# pico32_remote_v1_1.net
KiCad netlist of a schematic drawn in EAGLE
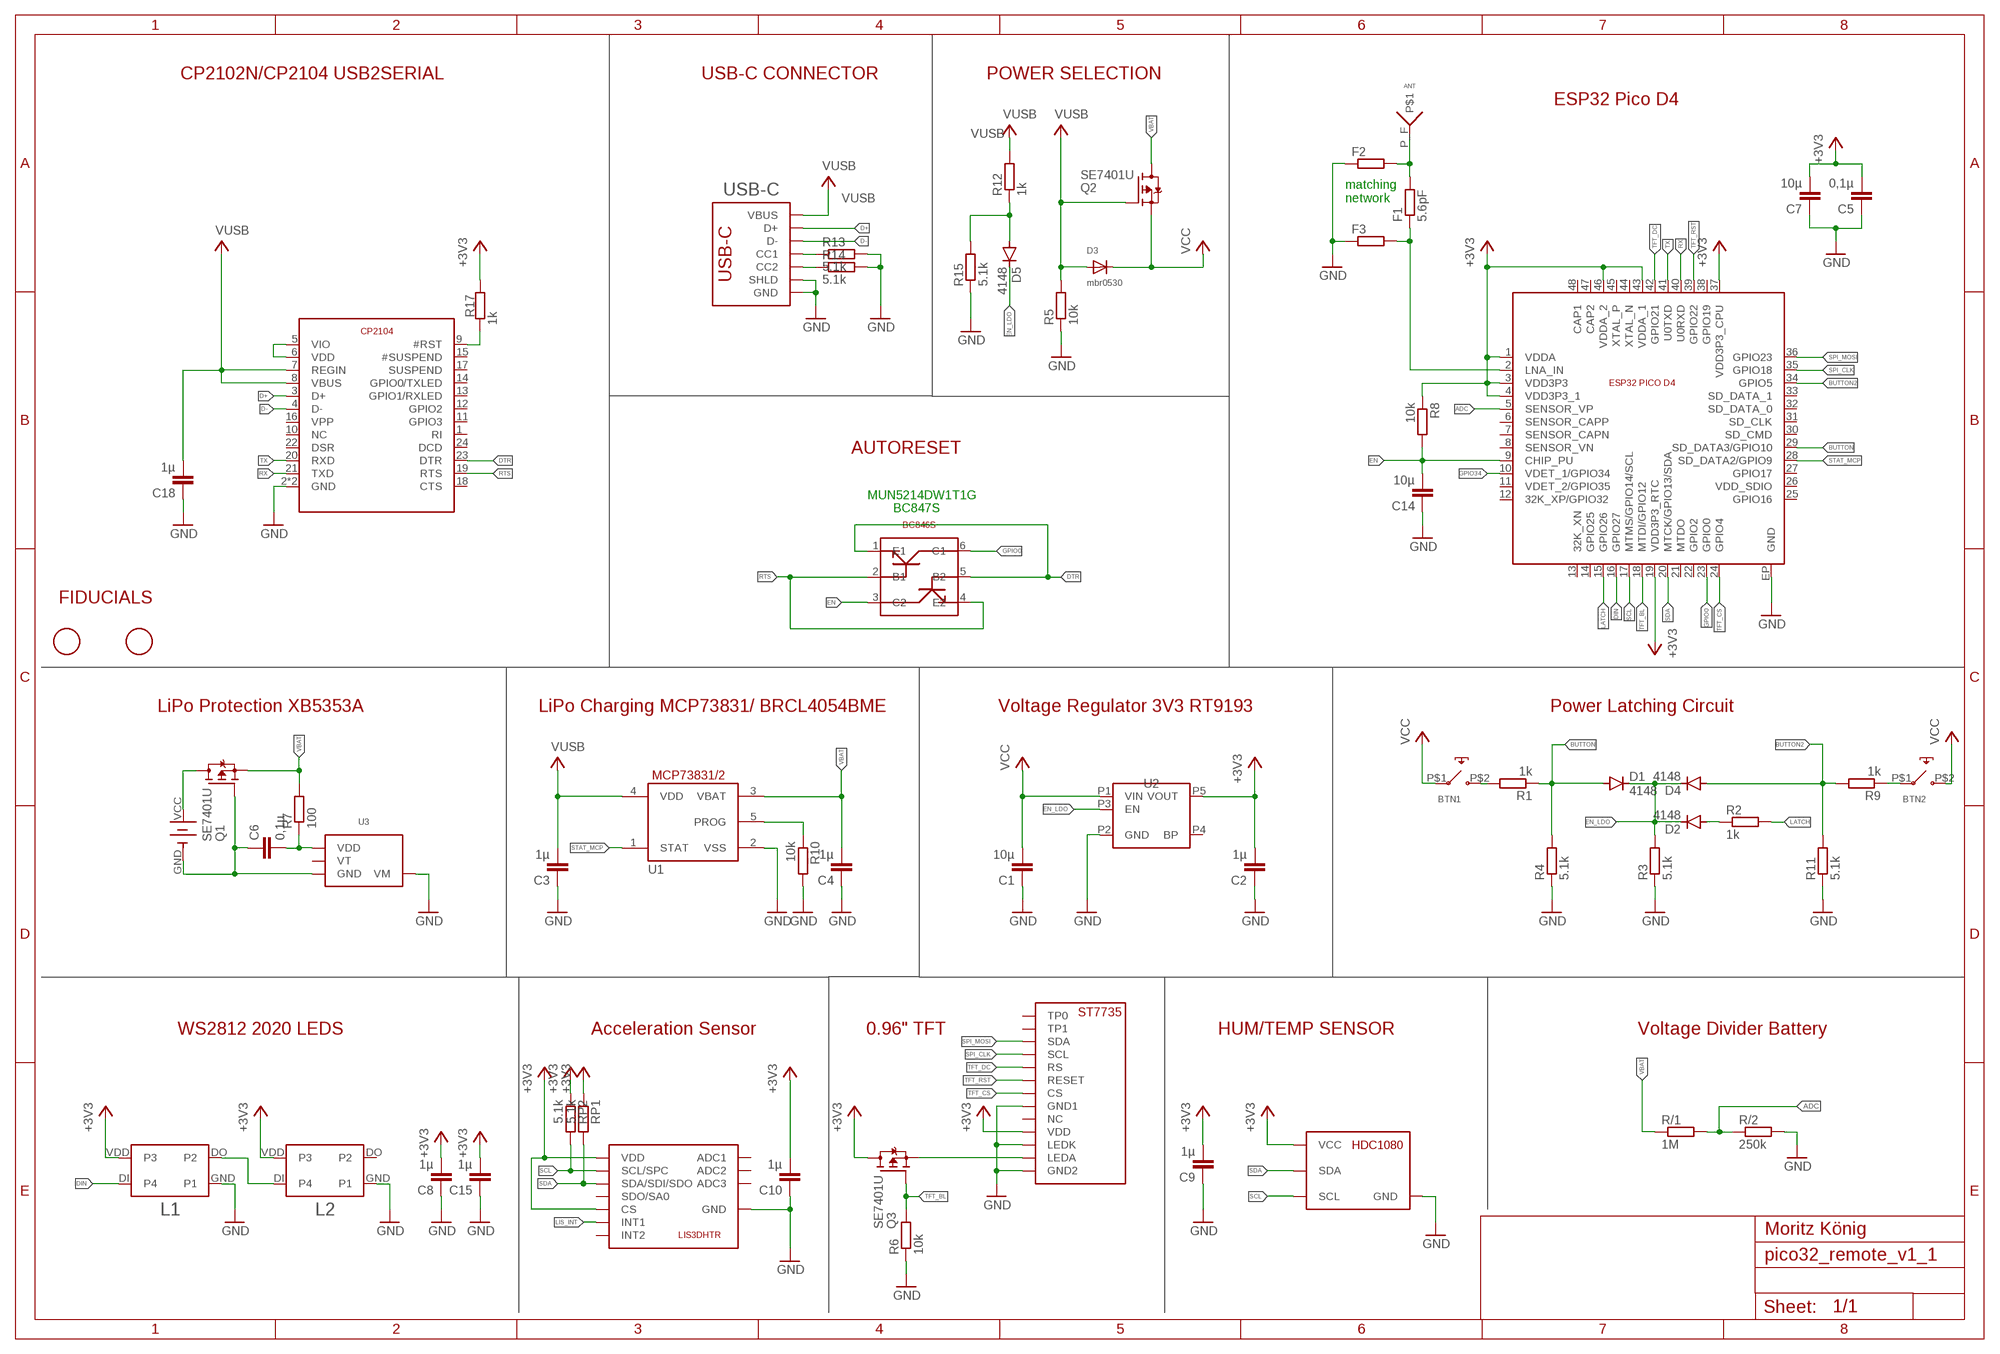
[diagram p0: schematic, sheet 1]

(export (version "E")
  (design (tool "Eeschema 10.0.6"))
  (components
    (comp (ref "ANT")
      (value "MOLEX_ANT_3D")
      (footprint "eagle-import:MOLEX_ANT_3D")
      (libsource (lib "eagle-import") (part "MOLEX_ANT_3D"))
    )
    (comp (ref "BTN1")
      (value "BUTTON_6X6_SILICON")
      (footprint "eagle-import:BUTTON_SILICON")
      (libsource (lib "eagle-import") (part "BUTTON_6X6_SILICON"))
    )
    (comp (ref "BTN2")
      (value "BUTTON_6X6_SILICON")
      (footprint "eagle-import:BUTTON_SILICON")
      (libsource (lib "eagle-import") (part "BUTTON_6X6_SILICON"))
    )
    (comp (ref "C1")
      (value "10µ")
      (footprint "eagle-import:C0603")
      (libsource (lib "eagle-import") (part "C-EU_WO_KEEPOUT"))
    )
    (comp (ref "C2")
      (value "1µ")
      (footprint "eagle-import:C0603")
      (libsource (lib "eagle-import") (part "C-EU_WO_KEEPOUT"))
    )
    (comp (ref "C3")
      (value "1µ")
      (footprint "eagle-import:R0402")
      (libsource (lib "eagle-import") (part "C-EU-0402-WOKEEPOUT_R"))
    )
    (comp (ref "C4")
      (value "1µ")
      (footprint "eagle-import:R0402")
      (libsource (lib "eagle-import") (part "C-EU-0402-WOKEEPOUT_R"))
    )
    (comp (ref "C5")
      (value "0,1µ")
      (footprint "eagle-import:C0603")
      (libsource (lib "eagle-import") (part "C-EU_WO_KEEPOUT"))
    )
    (comp (ref "C6")
      (value "0,1µ")
      (footprint "eagle-import:R0402")
      (libsource (lib "eagle-import") (part "C-EU-0402-WOKEEPOUT_R"))
    )
    (comp (ref "C7")
      (value "10µ")
      (footprint "eagle-import:C0603")
      (libsource (lib "eagle-import") (part "C-EU_WO_KEEPOUT"))
    )
    (comp (ref "C8")
      (value "1µ")
      (footprint "eagle-import:R0402")
      (libsource (lib "eagle-import") (part "C-EU-0402-WOKEEPOUT_R"))
    )
    (comp (ref "C9")
      (value "1µ")
      (footprint "eagle-import:R0402")
      (libsource (lib "eagle-import") (part "C-EU-0402-WOKEEPOUT_R"))
    )
    (comp (ref "C10")
      (value "1µ")
      (footprint "eagle-import:R0402")
      (libsource (lib "eagle-import") (part "C-EU-0402-WOKEEPOUT_R"))
    )
    (comp (ref "C14")
      (value "10µ")
      (footprint "eagle-import:C0402K")
      (libsource (lib "eagle-import") (part "C-EUC0402K"))
    )
    (comp (ref "C15")
      (value "1µ")
      (footprint "eagle-import:R0402")
      (libsource (lib "eagle-import") (part "C-EU-0402-WOKEEPOUT_R"))
    )
    (comp (ref "C18")
      (value "1µ")
      (footprint "eagle-import:R0402")
      (libsource (lib "eagle-import") (part "C-EU-0402-WOKEEPOUT_R"))
    )
    (comp (ref "D1")
      (value "4148")
      (footprint "eagle-import:SOD523")
      (libsource (lib "eagle-import") (part "DIODE-SOD523"))
    )
    (comp (ref "D2")
      (value "4148")
      (footprint "eagle-import:SOD523")
      (libsource (lib "eagle-import") (part "DIODE-SOD523"))
    )
    (comp (ref "D3")
      (value "mbr0530")
      (footprint "eagle-import:SOD-123FL")
      (libsource (lib "eagle-import") (part "DIODE_SOD-123FL"))
    )
    (comp (ref "D4")
      (value "4148")
      (footprint "eagle-import:SOD523")
      (libsource (lib "eagle-import") (part "DIODE-SOD523"))
    )
    (comp (ref "D5")
      (value "4148")
      (footprint "eagle-import:SOD523")
      (libsource (lib "eagle-import") (part "DIODE-SOD523"))
    )
    (comp (ref "ESP32")
      (value "ESP32_PICO_D4_LP")
      (footprint "eagle-import:QFN-48_LONG")
      (libsource (lib "eagle-import") (part "ESP32_PICO_D4_LP"))
    )
    (comp (ref "F1")
      (value "5.6pF")
      (footprint "eagle-import:R0402")
      (libsource (lib "eagle-import") (part "R-EU-0402-WOKEEPOUT"))
    )
    (comp (ref "F2")
      (value "R-EU-0402-WOKEEPOUT")
      (footprint "eagle-import:R0402")
      (libsource (lib "eagle-import") (part "R-EU-0402-WOKEEPOUT"))
    )
    (comp (ref "F3")
      (value "R-EU-0402-WOKEEPOUT")
      (footprint "eagle-import:R0402")
      (libsource (lib "eagle-import") (part "R-EU-0402-WOKEEPOUT"))
    )
    (comp (ref "L1")
      (value "WS2812_2020")
      (footprint "eagle-import:WS2812_2020")
      (libsource (lib "eagle-import") (part "WS2812_2020"))
    )
    (comp (ref "L2")
      (value "WS2812_2020")
      (footprint "eagle-import:WS2812_2020")
      (libsource (lib "eagle-import") (part "WS2812_2020"))
    )
    (comp (ref "Q1")
      (value "SE7401U")
      (footprint "eagle-import:SOT323")
      (libsource (lib "eagle-import") (part "SE7401U"))
    )
    (comp (ref "Q2")
      (value "SE7401U")
      (footprint "eagle-import:SOT323")
      (libsource (lib "eagle-import") (part "SE7401U"))
    )
    (comp (ref "Q3")
      (value "SE7401U")
      (footprint "eagle-import:SOT323")
      (libsource (lib "eagle-import") (part "SE7401U"))
    )
    (comp (ref "R/1")
      (value "1M")
      (footprint "eagle-import:R0402")
      (libsource (lib "eagle-import") (part "R-EU-0402-WOKEEPOUT"))
    )
    (comp (ref "R/2")
      (value "250k")
      (footprint "eagle-import:R0402")
      (libsource (lib "eagle-import") (part "R-EU-0402-WOKEEPOUT"))
    )
    (comp (ref "R1")
      (value "1k")
      (footprint "eagle-import:R0402")
      (libsource (lib "eagle-import") (part "R-EU-0402-WOKEEPOUT"))
    )
    (comp (ref "R2")
      (value "1k")
      (footprint "eagle-import:R0402")
      (libsource (lib "eagle-import") (part "R-EU-0402-WOKEEPOUT"))
    )
    (comp (ref "R3")
      (value "5.1k")
      (footprint "eagle-import:R0402")
      (libsource (lib "eagle-import") (part "R-EU-0402-WOKEEPOUT"))
    )
    (comp (ref "R4")
      (value "5.1k")
      (footprint "eagle-import:R0402")
      (libsource (lib "eagle-import") (part "R-EU-0402-WOKEEPOUT"))
    )
    (comp (ref "R5")
      (value "10k")
      (footprint "eagle-import:R0402")
      (libsource (lib "eagle-import") (part "R-EU-0402-WOKEEPOUT"))
    )
    (comp (ref "R6")
      (value "10k")
      (footprint "eagle-import:R0402")
      (libsource (lib "eagle-import") (part "R-EU-0402-WOKEEPOUT"))
    )
    (comp (ref "R7")
      (value "100")
      (footprint "eagle-import:R0402")
      (libsource (lib "eagle-import") (part "R-EU-0402-WOKEEPOUT"))
    )
    (comp (ref "R8")
      (value "10k")
      (footprint "eagle-import:R0402")
      (libsource (lib "eagle-import") (part "R-EU-0402-WOKEEPOUT"))
    )
    (comp (ref "R9")
      (value "1k")
      (footprint "eagle-import:R0402")
      (libsource (lib "eagle-import") (part "R-EU-0402-WOKEEPOUT"))
    )
    (comp (ref "R10")
      (value "10k")
      (footprint "eagle-import:R0402")
      (libsource (lib "eagle-import") (part "R-EU-0402-WOKEEPOUT"))
    )
    (comp (ref "R11")
      (value "5.1k")
      (footprint "eagle-import:R0402")
      (libsource (lib "eagle-import") (part "R-EU-0402-WOKEEPOUT"))
    )
    (comp (ref "R12")
      (value "1k")
      (footprint "eagle-import:R0402")
      (libsource (lib "eagle-import") (part "R-EU-0402-WOKEEPOUT"))
    )
    (comp (ref "R13")
      (value "5.1k")
      (footprint "eagle-import:R0402")
      (libsource (lib "eagle-import") (part "R-EU-0402-WOKEEPOUT"))
    )
    (comp (ref "R14")
      (value "5.1k")
      (footprint "eagle-import:R0402")
      (libsource (lib "eagle-import") (part "R-EU-0402-WOKEEPOUT"))
    )
    (comp (ref "R15")
      (value "5.1k")
      (footprint "eagle-import:R0402")
      (libsource (lib "eagle-import") (part "R-EU-0402-WOKEEPOUT"))
    )
    (comp (ref "R17")
      (value "1k")
      (footprint "eagle-import:R0402")
      (libsource (lib "eagle-import") (part "R-EU-0402-WOKEEPOUT"))
    )
    (comp (ref "RP1")
      (value "5.1k")
      (footprint "eagle-import:R0402")
      (libsource (lib "eagle-import") (part "R-EU-0402-WOKEEPOUT"))
    )
    (comp (ref "RP2")
      (value "5.1k")
      (footprint "eagle-import:R0402")
      (libsource (lib "eagle-import") (part "R-EU-0402-WOKEEPOUT"))
    )
    (comp (ref "U$2")
      (value "2450_BATTERYHOLDER_SMD")
      (footprint "eagle-import:2450_BATTERYHOLDER_SMD")
      (libsource (lib "eagle-import") (part "2450_BATTERYHOLDER_SMD"))
    )
    (comp (ref "U$4")
      (value "ST7735_096TFT_TWISTED")
      (footprint "eagle-import:ST7735_096TFT_TWISTED")
      (libsource (lib "eagle-import") (part "ST7735_096TFT_TWISTED"))
    )
    (comp (ref "U$6")
      (value "FIDUCIAL")
      (footprint "eagle-import:FIDUCIAL_1MM")
      (libsource (lib "eagle-import") (part "FIDUCIAL"))
    )
    (comp (ref "U$7")
      (value "FIDUCIAL")
      (footprint "eagle-import:FIDUCIAL_1MM")
      (libsource (lib "eagle-import") (part "FIDUCIAL"))
    )
    (comp (ref "U1")
      (value "BRCL4054BME")
      (footprint "eagle-import:SOT23-5L")
      (libsource (lib "eagle-import") (part "MCP73831/OT"))
    )
    (comp (ref "U2")
      (value "RT9193_SC70-5")
      (footprint "eagle-import:SC-70-5")
      (libsource (lib "eagle-import") (part "RT9193_SC70-5"))
    )
    (comp (ref "U3")
      (value "XB5353A")
      (footprint "eagle-import:SOT23-5")
      (libsource (lib "eagle-import") (part "XB5353A"))
    )
    (comp (ref "U4")
      (value "LIS3DHTR")
      (footprint "eagle-import:LGA_16_LIS3DHTR")
      (libsource (lib "eagle-import") (part "LIS3DHTR"))
    )
    (comp (ref "U5")
      (value "CP2102N")
      (footprint "eagle-import:QFN24-4X4")
      (libsource (lib "eagle-import") (part "CP2104"))
    )
    (comp (ref "U6")
      (value "MUN5214DW1T1G")
      (footprint "eagle-import:SOT363")
      (libsource (lib "eagle-import") (part "BC846S"))
    )
    (comp (ref "U7")
      (value "HDC1080")
      (footprint "eagle-import:WSON08_HDC1080")
      (libsource (lib "eagle-import") (part "HDC1080"))
    )
    (comp (ref "USB-C")
      (value "USB_C_C393939")
      (footprint "eagle-import:USBC_C393939")
      (libsource (lib "eagle-import") (part "USB_C_C393939"))
    )
  )
  (nets
    (net (code "1") (name "+3V3") (class "Default")
      (node (ref "C10") (pin "2") (pinfunction "2_2") (pintype "passive"))
      (node (ref "C15") (pin "2") (pinfunction "2_2") (pintype "passive"))
      (node (ref "C2") (pin "2") (pinfunction "2_2") (pintype "passive"))
      (node (ref "C5") (pin "2") (pinfunction "2_2") (pintype "passive"))
      (node (ref "C7") (pin "2") (pinfunction "2_2") (pintype "passive"))
      (node (ref "C8") (pin "2") (pinfunction "2_2") (pintype "passive"))
      (node (ref "C9") (pin "2") (pinfunction "2_2") (pintype "passive"))
      (node (ref "ESP32") (pin "1") (pinfunction "VDDA_1") (pintype "bidirectional"))
      (node (ref "ESP32") (pin "19") (pinfunction "VDD3P3_RTC_19") (pintype "bidirectional"))
      (node (ref "ESP32") (pin "3") (pinfunction "VDD3P3_3") (pintype "bidirectional"))
      (node (ref "ESP32") (pin "37") (pinfunction "VDD3P3_CPU_37") (pintype "bidirectional"))
      (node (ref "ESP32") (pin "4") (pinfunction "VDD3P3_1_4") (pintype "bidirectional"))
      (node (ref "ESP32") (pin "43") (pinfunction "VDDA_1_43") (pintype "bidirectional"))
      (node (ref "ESP32") (pin "46") (pinfunction "VDDA_2_46") (pintype "bidirectional"))
      (node (ref "L1") (pin "VDD") (pinfunction "P3_VDD") (pintype "bidirectional"))
      (node (ref "L2") (pin "VDD") (pinfunction "P3_VDD") (pintype "bidirectional"))
      (node (ref "Q3") (pin "3") (pinfunction "D_3") (pintype "passive"))
      (node (ref "R17") (pin "2") (pinfunction "2_2") (pintype "passive"))
      (node (ref "R8") (pin "1") (pinfunction "1_1") (pintype "passive"))
      (node (ref "RP1") (pin "1") (pinfunction "1_1") (pintype "passive"))
      (node (ref "RP2") (pin "1") (pinfunction "1_1") (pintype "passive"))
      (node (ref "U$4") (pin "P10") (pinfunction "VDD_P10") (pintype "bidirectional"))
      (node (ref "U2") (pin "P5") (pinfunction "VOUT_P5") (pintype "bidirectional"))
      (node (ref "U4") (pin "P$1") (pinfunction "VDD_P$1") (pintype "bidirectional"))
      (node (ref "U4") (pin "P$14") (pinfunction "VDD_P$14") (pintype "bidirectional"))
      (node (ref "U4") (pin "P$8") (pinfunction "CS_P$8") (pintype "bidirectional"))
      (node (ref "U7") (pin "P5") (pinfunction "VCC_P5") (pintype "bidirectional"))
    )
    (net (code "2") (name "ADC") (class "Default")
      (node (ref "ESP32") (pin "5") (pinfunction "SENSOR_VP_5") (pintype "bidirectional"))
      (node (ref "R/1") (pin "2") (pinfunction "2_2") (pintype "passive"))
      (node (ref "R/2") (pin "1") (pinfunction "1_1") (pintype "passive"))
    )
    (net (code "3") (name "BUTTON") (class "Default")
      (node (ref "D1") (pin "A") (pinfunction "A_A") (pintype "passive"))
      (node (ref "ESP32") (pin "29") (pinfunction "SD_DATA3/GPIO10_29") (pintype "bidirectional"))
      (node (ref "R1") (pin "1") (pinfunction "1_1") (pintype "passive"))
      (node (ref "R4") (pin "2") (pinfunction "2_2") (pintype "passive"))
    )
    (net (code "4") (name "BUTTON2") (class "Default")
      (node (ref "D4") (pin "A") (pinfunction "A_A") (pintype "passive"))
      (node (ref "ESP32") (pin "34") (pinfunction "GPIO5_34") (pintype "bidirectional"))
      (node (ref "R11") (pin "2") (pinfunction "2_2") (pintype "passive"))
      (node (ref "R9") (pin "2") (pinfunction "2_2") (pintype "passive"))
    )
    (net (code "5") (name "D+") (class "Default")
      (node (ref "U5") (pin "3") (pinfunction "D+_3") (pintype "bidirectional"))
      (node (ref "USB-C") (pin "A6") (pinfunction "D+_A6") (pintype "bidirectional"))
      (node (ref "USB-C") (pin "B6") (pinfunction "D+_B6") (pintype "bidirectional"))
    )
    (net (code "6") (name "D-") (class "Default")
      (node (ref "U5") (pin "4") (pinfunction "D-_4") (pintype "bidirectional"))
      (node (ref "USB-C") (pin "A7") (pinfunction "D-_A7") (pintype "bidirectional"))
      (node (ref "USB-C") (pin "B7") (pinfunction "D-_B7") (pintype "bidirectional"))
    )
    (net (code "7") (name "DIN") (class "Default")
      (node (ref "ESP32") (pin "16") (pinfunction "GPIO27_16") (pintype "bidirectional"))
      (node (ref "L1") (pin "DI") (pinfunction "P4_DI") (pintype "bidirectional"))
    )
    (net (code "8") (name "DTR") (class "Default")
      (node (ref "U5") (pin "23") (pinfunction "DTR_23") (pintype "bidirectional"))
      (node (ref "U6") (pin "1") (pinfunction "E1_1") (pintype "bidirectional"))
      (node (ref "U6") (pin "5") (pinfunction "B2_5") (pintype "bidirectional"))
    )
    (net (code "9") (name "EN") (class "Default")
      (node (ref "C14") (pin "2") (pinfunction "2_2") (pintype "passive"))
      (node (ref "ESP32") (pin "9") (pinfunction "CHIP_PU_9") (pintype "bidirectional"))
      (node (ref "R8") (pin "2") (pinfunction "2_2") (pintype "passive"))
      (node (ref "U6") (pin "3") (pinfunction "C2_3") (pintype "bidirectional"))
    )
    (net (code "10") (name "EN_LDO") (class "Default")
      (node (ref "D1") (pin "C") (pinfunction "C_C") (pintype "passive"))
      (node (ref "D2") (pin "C") (pinfunction "C_C") (pintype "passive"))
      (node (ref "D4") (pin "C") (pinfunction "C_C") (pintype "passive"))
      (node (ref "D5") (pin "C") (pinfunction "C_C") (pintype "passive"))
      (node (ref "R3") (pin "2") (pinfunction "2_2") (pintype "passive"))
      (node (ref "U2") (pin "P3") (pinfunction "EN_P3") (pintype "bidirectional"))
    )
    (net (code "11") (name "GND") (class "Default")
      (node (ref "C1") (pin "1") (pinfunction "1_1") (pintype "passive"))
      (node (ref "C10") (pin "1") (pinfunction "1_1") (pintype "passive"))
      (node (ref "C14") (pin "1") (pinfunction "1_1") (pintype "passive"))
      (node (ref "C15") (pin "1") (pinfunction "1_1") (pintype "passive"))
      (node (ref "C18") (pin "1") (pinfunction "1_1") (pintype "passive"))
      (node (ref "C2") (pin "1") (pinfunction "1_1") (pintype "passive"))
      (node (ref "C3") (pin "1") (pinfunction "1_1") (pintype "passive"))
      (node (ref "C4") (pin "1") (pinfunction "1_1") (pintype "passive"))
      (node (ref "C5") (pin "1") (pinfunction "1_1") (pintype "passive"))
      (node (ref "C7") (pin "1") (pinfunction "1_1") (pintype "passive"))
      (node (ref "C8") (pin "1") (pinfunction "1_1") (pintype "passive"))
      (node (ref "C9") (pin "1") (pinfunction "1_1") (pintype "passive"))
      (node (ref "ESP32") (pin "EP") (pinfunction "GND_EP") (pintype "bidirectional"))
      (node (ref "F2") (pin "1") (pinfunction "1_1") (pintype "passive"))
      (node (ref "F3") (pin "1") (pinfunction "1_1") (pintype "passive"))
      (node (ref "L1") (pin "GND") (pinfunction "P1_GND") (pintype "bidirectional"))
      (node (ref "L2") (pin "GND") (pinfunction "P1_GND") (pintype "bidirectional"))
      (node (ref "R/2") (pin "2") (pinfunction "2_2") (pintype "passive"))
      (node (ref "R10") (pin "2") (pinfunction "2_2") (pintype "passive"))
      (node (ref "R11") (pin "1") (pinfunction "1_1") (pintype "passive"))
      (node (ref "R13") (pin "2") (pinfunction "2_2") (pintype "passive"))
      (node (ref "R14") (pin "2") (pinfunction "2_2") (pintype "passive"))
      (node (ref "R15") (pin "1") (pinfunction "1_1") (pintype "passive"))
      (node (ref "R3") (pin "1") (pinfunction "1_1") (pintype "passive"))
      (node (ref "R4") (pin "1") (pinfunction "1_1") (pintype "passive"))
      (node (ref "R5") (pin "1") (pinfunction "1_1") (pintype "passive"))
      (node (ref "R6") (pin "1") (pinfunction "1_1") (pintype "passive"))
      (node (ref "U$4") (pin "P11") (pinfunction "LEDK_P11") (pintype "bidirectional"))
      (node (ref "U$4") (pin "P13") (pinfunction "GND2_P13") (pintype "bidirectional"))
      (node (ref "U$4") (pin "P8") (pinfunction "GND1_P8") (pintype "bidirectional"))
      (node (ref "U1") (pin "2") (pinfunction "VSS_2") (pintype "power_in"))
      (node (ref "U2") (pin "P2") (pinfunction "GND_P2") (pintype "bidirectional"))
      (node (ref "U3") (pin "4") (pinfunction "VM_4") (pintype "bidirectional"))
      (node (ref "U3") (pin "5") (pinfunction "VM_5") (pintype "bidirectional"))
      (node (ref "U4") (pin "P$10") (pinfunction "GND_P$10") (pintype "bidirectional"))
      (node (ref "U4") (pin "P$12") (pinfunction "GND_P$12") (pintype "bidirectional"))
      (node (ref "U4") (pin "P$5") (pinfunction "GND_P$5") (pintype "bidirectional"))
      (node (ref "U5") (pin "2") (pinfunction "GND_2") (pintype "bidirectional"))
      (node (ref "U5") (pin "EXP") (pinfunction "GND_EXP") (pintype "bidirectional"))
      (node (ref "U7") (pin "P2") (pinfunction "GND_P2") (pintype "bidirectional"))
      (node (ref "USB-C") (pin "A1B12") (pinfunction "GND_A1B12") (pintype "bidirectional"))
      (node (ref "USB-C") (pin "B1A12") (pinfunction "GND_B1A12") (pintype "bidirectional"))
      (node (ref "USB-C") (pin "S1") (pinfunction "SHLD_S1") (pintype "bidirectional"))
      (node (ref "USB-C") (pin "S2") (pinfunction "SHLD_S2") (pintype "bidirectional"))
      (node (ref "USB-C") (pin "S3") (pinfunction "SHLD_S3") (pintype "bidirectional"))
      (node (ref "USB-C") (pin "S4") (pinfunction "SHLD_S4") (pintype "bidirectional"))
    )
    (net (code "12") (name "GPIO0") (class "Default")
      (node (ref "ESP32") (pin "23") (pinfunction "GPIO0_23") (pintype "bidirectional"))
      (node (ref "U6") (pin "6") (pinfunction "C1_6") (pintype "bidirectional"))
    )
    (net (code "13") (name "GPIO34") (class "Default")
      (node (ref "ESP32") (pin "10") (pinfunction "VDET_1/GPIO34_10") (pintype "bidirectional"))
    )
    (net (code "14") (name "LATCH") (class "Default")
      (node (ref "ESP32") (pin "15") (pinfunction "GPIO26_15") (pintype "bidirectional"))
      (node (ref "R2") (pin "2") (pinfunction "2_2") (pintype "passive"))
    )
    (net (code "15") (name "LIS_INT") (class "Default")
      (node (ref "U4") (pin "P$11") (pinfunction "INT1_P$11") (pintype "bidirectional"))
    )
    (net (code "16") (name "Net-(ANT-P$1)") (class "Default")
      (node (ref "ANT") (pin "P_F") (pinfunction "P$1_P_F") (pintype "bidirectional"))
      (node (ref "F1") (pin "2") (pinfunction "2_2") (pintype "passive"))
      (node (ref "F2") (pin "2") (pinfunction "2_2") (pintype "passive"))
    )
    (net (code "17") (name "Net-(BTN1-P2)") (class "Default")
      (node (ref "BTN1") (pin "P$2") (pinfunction "P2_P$2") (pintype "bidirectional"))
      (node (ref "R1") (pin "2") (pinfunction "2_2") (pintype "passive"))
    )
    (net (code "18") (name "Net-(BTN2-P1)") (class "Default")
      (node (ref "BTN2") (pin "P$1") (pinfunction "P1_P$1") (pintype "bidirectional"))
      (node (ref "R9") (pin "1") (pinfunction "1_1") (pintype "passive"))
    )
    (net (code "19") (name "Net-(D2-PadA)") (class "Default")
      (node (ref "D2") (pin "A") (pinfunction "A_A") (pintype "passive"))
      (node (ref "R2") (pin "1") (pinfunction "1_1") (pintype "passive"))
    )
    (net (code "20") (name "Net-(D5-PadA)") (class "Default")
      (node (ref "D5") (pin "A") (pinfunction "A_A") (pintype "passive"))
      (node (ref "R12") (pin "1") (pinfunction "1_1") (pintype "passive"))
      (node (ref "R15") (pin "2") (pinfunction "2_2") (pintype "passive"))
    )
    (net (code "21") (name "Net-(ESP32-LNA_IN)") (class "Default")
      (node (ref "ESP32") (pin "2") (pinfunction "LNA_IN_2") (pintype "bidirectional"))
      (node (ref "F1") (pin "1") (pinfunction "1_1") (pintype "passive"))
      (node (ref "F3") (pin "2") (pinfunction "2_2") (pintype "passive"))
    )
    (net (code "22") (name "Net-(L1-P2)") (class "Default")
      (node (ref "L1") (pin "DO") (pinfunction "P2_DO") (pintype "bidirectional"))
      (node (ref "L2") (pin "DI") (pinfunction "P4_DI") (pintype "bidirectional"))
    )
    (net (code "23") (name "Net-(Q1-D)") (class "Default")
      (node (ref "Q1") (pin "3") (pinfunction "D_3") (pintype "passive"))
      (node (ref "U$2") (pin "VCC") (pinfunction "VCC_VCC") (pintype "bidirectional"))
    )
    (net (code "24") (name "Net-(Q1-G)") (class "Default")
      (node (ref "C6") (pin "1") (pinfunction "1_1") (pintype "passive"))
      (node (ref "Q1") (pin "1") (pinfunction "G_1") (pintype "passive"))
      (node (ref "U$2") (pin "GND") (pinfunction "GND_GND") (pintype "bidirectional"))
      (node (ref "U3") (pin "2") (pinfunction "GND_2") (pintype "bidirectional"))
    )
    (net (code "25") (name "Net-(Q3-S)") (class "Default")
      (node (ref "Q3") (pin "2") (pinfunction "S_2") (pintype "passive"))
      (node (ref "U$4") (pin "P12") (pinfunction "LEDA_P12") (pintype "bidirectional"))
    )
    (net (code "26") (name "Net-(U1-PROG)") (class "Default")
      (node (ref "R10") (pin "1") (pinfunction "1_1") (pintype "passive"))
      (node (ref "U1") (pin "5") (pinfunction "PROG_5") (pintype "input"))
    )
    (net (code "27") (name "Net-(U3-VDD)") (class "Default")
      (node (ref "C6") (pin "2") (pinfunction "2_2") (pintype "passive"))
      (node (ref "R7") (pin "1") (pinfunction "1_1") (pintype "passive"))
      (node (ref "U3") (pin "3") (pinfunction "VDD_3") (pintype "bidirectional"))
    )
    (net (code "28") (name "Net-(U5-#RST)") (class "Default")
      (node (ref "R17") (pin "1") (pinfunction "1_1") (pintype "passive"))
      (node (ref "U5") (pin "9") (pinfunction "#RST_9") (pintype "bidirectional"))
    )
    (net (code "29") (name "Net-(U5-VDD)") (class "Default")
      (node (ref "U5") (pin "5") (pinfunction "VIO_5") (pintype "bidirectional"))
      (node (ref "U5") (pin "6") (pinfunction "VDD_6") (pintype "bidirectional"))
    )
    (net (code "30") (name "Net-(USB-C-CC1)") (class "Default")
      (node (ref "R13") (pin "1") (pinfunction "1_1") (pintype "passive"))
      (node (ref "USB-C") (pin "A5") (pinfunction "CC1_A5") (pintype "bidirectional"))
    )
    (net (code "31") (name "Net-(USB-C-CC2)") (class "Default")
      (node (ref "R14") (pin "1") (pinfunction "1_1") (pintype "passive"))
      (node (ref "USB-C") (pin "B5") (pinfunction "CC2_B5") (pintype "bidirectional"))
    )
    (net (code "32") (name "RTS") (class "Default")
      (node (ref "U5") (pin "19") (pinfunction "RTS_19") (pintype "bidirectional"))
      (node (ref "U6") (pin "2") (pinfunction "B1_2") (pintype "bidirectional"))
      (node (ref "U6") (pin "4") (pinfunction "E2_4") (pintype "bidirectional"))
    )
    (net (code "33") (name "RX") (class "Default")
      (node (ref "ESP32") (pin "40") (pinfunction "U0RXD_40") (pintype "bidirectional"))
      (node (ref "U5") (pin "21") (pinfunction "TXD_21") (pintype "bidirectional"))
    )
    (net (code "34") (name "SCL") (class "Default")
      (node (ref "ESP32") (pin "17") (pinfunction "MTMS/GPIO14/SCL_17") (pintype "bidirectional"))
      (node (ref "RP2") (pin "2") (pinfunction "2_2") (pintype "passive"))
      (node (ref "U4") (pin "P$4") (pinfunction "SCL/SPC_P$4") (pintype "bidirectional"))
      (node (ref "U7") (pin "P6") (pinfunction "SCL_P6") (pintype "bidirectional"))
    )
    (net (code "35") (name "SDA") (class "Default")
      (node (ref "ESP32") (pin "20") (pinfunction "MTCK/GPIO13/SDA_20") (pintype "bidirectional"))
      (node (ref "RP1") (pin "2") (pinfunction "2_2") (pintype "passive"))
      (node (ref "U4") (pin "P$6") (pinfunction "SDA/SDI/SDO_P$6") (pintype "bidirectional"))
      (node (ref "U7") (pin "P1") (pinfunction "SDA_P1") (pintype "bidirectional"))
    )
    (net (code "36") (name "SPI_CLK") (class "Default")
      (node (ref "ESP32") (pin "35") (pinfunction "GPIO18_35") (pintype "bidirectional"))
      (node (ref "U$4") (pin "P4") (pinfunction "SCL_P4") (pintype "bidirectional"))
    )
    (net (code "37") (name "SPI_MOSI") (class "Default")
      (node (ref "ESP32") (pin "36") (pinfunction "GPIO23_36") (pintype "bidirectional"))
      (node (ref "U$4") (pin "P3") (pinfunction "SDA_P3") (pintype "bidirectional"))
    )
    (net (code "38") (name "STAT_MCP") (class "Default")
      (node (ref "ESP32") (pin "28") (pinfunction "SD_DATA2/GPIO9_28") (pintype "bidirectional"))
      (node (ref "U1") (pin "1") (pinfunction "STAT_1") (pintype "output"))
    )
    (net (code "39") (name "TFT_BL") (class "Default")
      (node (ref "ESP32") (pin "18") (pinfunction "MTDI/GPIO12_18") (pintype "bidirectional"))
      (node (ref "Q3") (pin "1") (pinfunction "G_1") (pintype "passive"))
      (node (ref "R6") (pin "2") (pinfunction "2_2") (pintype "passive"))
    )
    (net (code "40") (name "TFT_CS") (class "Default")
      (node (ref "ESP32") (pin "24") (pinfunction "GPIO4_24") (pintype "bidirectional"))
      (node (ref "U$4") (pin "P7") (pinfunction "CS_P7") (pintype "bidirectional"))
    )
    (net (code "41") (name "TFT_DC") (class "Default")
      (node (ref "ESP32") (pin "42") (pinfunction "GPIO21_42") (pintype "bidirectional"))
      (node (ref "U$4") (pin "P5") (pinfunction "RS_P5") (pintype "bidirectional"))
    )
    (net (code "42") (name "TFT_RST") (class "Default")
      (node (ref "ESP32") (pin "39") (pinfunction "GPIO22_39") (pintype "bidirectional"))
      (node (ref "U$4") (pin "P6") (pinfunction "RESET_P6") (pintype "bidirectional"))
    )
    (net (code "43") (name "TX") (class "Default")
      (node (ref "ESP32") (pin "41") (pinfunction "U0TXD_41") (pintype "bidirectional"))
      (node (ref "U5") (pin "20") (pinfunction "RXD_20") (pintype "bidirectional"))
    )
    (net (code "44") (name "VBAT") (class "Default")
      (node (ref "C4") (pin "2") (pinfunction "2_2") (pintype "passive"))
      (node (ref "Q1") (pin "2") (pinfunction "S_2") (pintype "passive"))
      (node (ref "Q2") (pin "3") (pinfunction "D_3") (pintype "passive"))
      (node (ref "R/1") (pin "1") (pinfunction "1_1") (pintype "passive"))
      (node (ref "R7") (pin "2") (pinfunction "2_2") (pintype "passive"))
      (node (ref "U1") (pin "3") (pinfunction "VBAT_3") (pintype "bidirectional"))
    )
    (net (code "45") (name "VCC") (class "Default")
      (node (ref "BTN1") (pin "P$1") (pinfunction "P1_P$1") (pintype "bidirectional"))
      (node (ref "BTN2") (pin "P$2") (pinfunction "P2_P$2") (pintype "bidirectional"))
      (node (ref "C1") (pin "2") (pinfunction "2_2") (pintype "passive"))
      (node (ref "D3") (pin "C") (pinfunction "C_C") (pintype "passive"))
      (node (ref "Q2") (pin "2") (pinfunction "S_2") (pintype "passive"))
      (node (ref "U2") (pin "P1") (pinfunction "VIN_P1") (pintype "bidirectional"))
    )
    (net (code "46") (name "VUSB") (class "Default")
      (node (ref "C18") (pin "2") (pinfunction "2_2") (pintype "passive"))
      (node (ref "C3") (pin "2") (pinfunction "2_2") (pintype "passive"))
      (node (ref "D3") (pin "A") (pinfunction "A_A") (pintype "passive"))
      (node (ref "Q2") (pin "1") (pinfunction "G_1") (pintype "passive"))
      (node (ref "R12") (pin "2") (pinfunction "2_2") (pintype "passive"))
      (node (ref "R5") (pin "2") (pinfunction "2_2") (pintype "passive"))
      (node (ref "U1") (pin "4") (pinfunction "VDD_4") (pintype "power_in"))
      (node (ref "U5") (pin "7") (pinfunction "REGIN_7") (pintype "bidirectional"))
      (node (ref "U5") (pin "8") (pinfunction "VBUS_8") (pintype "bidirectional"))
      (node (ref "USB-C") (pin "A4B9") (pinfunction "VBUS_A4B9") (pintype "bidirectional"))
      (node (ref "USB-C") (pin "B4A9") (pinfunction "VBUS_B4A9") (pintype "bidirectional"))
    )
    (net (code "47") (name "unconnected-(ESP32-32K_XN-Pad13)") (class "Default")
      (node (ref "ESP32") (pin "13") (pinfunction "32K_XN_13") (pintype "bidirectional"))
    )
    (net (code "48") (name "unconnected-(ESP32-32K_XP{slash}GPIO32-Pad12)") (class "Default")
      (node (ref "ESP32") (pin "12") (pinfunction "32K_XP/GPIO32_12") (pintype "bidirectional"))
    )
    (net (code "49") (name "unconnected-(ESP32-CAP1-Pad48)") (class "Default")
      (node (ref "ESP32") (pin "48") (pinfunction "CAP1_48") (pintype "bidirectional"))
    )
    (net (code "50") (name "unconnected-(ESP32-CAP2-Pad47)") (class "Default")
      (node (ref "ESP32") (pin "47") (pinfunction "CAP2_47") (pintype "bidirectional"))
    )
    (net (code "51") (name "unconnected-(ESP32-GPIO2-Pad22)") (class "Default")
      (node (ref "ESP32") (pin "22") (pinfunction "GPIO2_22") (pintype "bidirectional"))
    )
    (net (code "52") (name "unconnected-(ESP32-GPIO16-Pad25)") (class "Default")
      (node (ref "ESP32") (pin "25") (pinfunction "GPIO16_25") (pintype "bidirectional"))
    )
    (net (code "53") (name "unconnected-(ESP32-GPIO17-Pad27)") (class "Default")
      (node (ref "ESP32") (pin "27") (pinfunction "GPIO17_27") (pintype "bidirectional"))
    )
    (net (code "54") (name "unconnected-(ESP32-GPIO19-Pad38)") (class "Default")
      (node (ref "ESP32") (pin "38") (pinfunction "GPIO19_38") (pintype "bidirectional"))
    )
    (net (code "55") (name "unconnected-(ESP32-GPIO25-Pad14)") (class "Default")
      (node (ref "ESP32") (pin "14") (pinfunction "GPIO25_14") (pintype "bidirectional"))
    )
    (net (code "56") (name "unconnected-(ESP32-MTDO-Pad21)") (class "Default")
      (node (ref "ESP32") (pin "21") (pinfunction "MTDO_21") (pintype "bidirectional"))
    )
    (net (code "57") (name "unconnected-(ESP32-SD_CLK-Pad31)") (class "Default")
      (node (ref "ESP32") (pin "31") (pinfunction "SD_CLK_31") (pintype "bidirectional"))
    )
    (net (code "58") (name "unconnected-(ESP32-SD_CMD-Pad30)") (class "Default")
      (node (ref "ESP32") (pin "30") (pinfunction "SD_CMD_30") (pintype "bidirectional"))
    )
    (net (code "59") (name "unconnected-(ESP32-SD_DATA_0-Pad32)") (class "Default")
      (node (ref "ESP32") (pin "32") (pinfunction "SD_DATA_0_32") (pintype "bidirectional"))
    )
    (net (code "60") (name "unconnected-(ESP32-SD_DATA_1-Pad33)") (class "Default")
      (node (ref "ESP32") (pin "33") (pinfunction "SD_DATA_1_33") (pintype "bidirectional"))
    )
    (net (code "61") (name "unconnected-(ESP32-SENSOR_CAPN-Pad7)") (class "Default")
      (node (ref "ESP32") (pin "7") (pinfunction "SENSOR_CAPN_7") (pintype "bidirectional"))
    )
    (net (code "62") (name "unconnected-(ESP32-SENSOR_CAPP-Pad6)") (class "Default")
      (node (ref "ESP32") (pin "6") (pinfunction "SENSOR_CAPP_6") (pintype "bidirectional"))
    )
    (net (code "63") (name "unconnected-(ESP32-SENSOR_VN-Pad8)") (class "Default")
      (node (ref "ESP32") (pin "8") (pinfunction "SENSOR_VN_8") (pintype "bidirectional"))
    )
    (net (code "64") (name "unconnected-(ESP32-VDD_SDIO-Pad26)") (class "Default")
      (node (ref "ESP32") (pin "26") (pinfunction "VDD_SDIO_26") (pintype "bidirectional"))
    )
    (net (code "65") (name "unconnected-(ESP32-VDET_2{slash}GPIO35-Pad11)") (class "Default")
      (node (ref "ESP32") (pin "11") (pinfunction "VDET_2/GPIO35_11") (pintype "bidirectional"))
    )
    (net (code "66") (name "unconnected-(ESP32-XTAL_N-Pad44)") (class "Default")
      (node (ref "ESP32") (pin "44") (pinfunction "XTAL_N_44") (pintype "bidirectional"))
    )
    (net (code "67") (name "unconnected-(ESP32-XTAL_P-Pad45)") (class "Default")
      (node (ref "ESP32") (pin "45") (pinfunction "XTAL_P_45") (pintype "bidirectional"))
    )
    (net (code "68") (name "unconnected-(L2-P2-PadDO)") (class "Default")
      (node (ref "L2") (pin "DO") (pinfunction "P2_DO") (pintype "bidirectional"))
    )
    (net (code "69") (name "unconnected-(U$4-NC-PadP9)") (class "Default")
      (node (ref "U$4") (pin "P9") (pinfunction "NC_P9") (pintype "bidirectional"))
    )
    (net (code "70") (name "unconnected-(U$4-TP0-PadP1)") (class "Default")
      (node (ref "U$4") (pin "P1") (pinfunction "TP0_P1") (pintype "bidirectional"))
    )
    (net (code "71") (name "unconnected-(U$4-TP1-PadP2)") (class "Default")
      (node (ref "U$4") (pin "P2") (pinfunction "TP1_P2") (pintype "bidirectional"))
    )
    (net (code "72") (name "unconnected-(U2-BP-PadP4)") (class "Default")
      (node (ref "U2") (pin "P4") (pinfunction "BP_P4") (pintype "bidirectional"))
    )
    (net (code "73") (name "unconnected-(U3-VT-Pad1)") (class "Default")
      (node (ref "U3") (pin "1") (pinfunction "VT_1") (pintype "bidirectional"))
    )
    (net (code "74") (name "unconnected-(U4-ADC1-PadP$16)") (class "Default")
      (node (ref "U4") (pin "P$16") (pinfunction "ADC1_P$16") (pintype "bidirectional"))
    )
    (net (code "75") (name "unconnected-(U4-ADC2-PadP$15)") (class "Default")
      (node (ref "U4") (pin "P$15") (pinfunction "ADC2_P$15") (pintype "bidirectional"))
    )
    (net (code "76") (name "unconnected-(U4-ADC3-PadP$13)") (class "Default")
      (node (ref "U4") (pin "P$13") (pinfunction "ADC3_P$13") (pintype "bidirectional"))
    )
    (net (code "77") (name "unconnected-(U4-INT2-PadP$9)") (class "Default")
      (node (ref "U4") (pin "P$9") (pinfunction "INT2_P$9") (pintype "bidirectional"))
    )
    (net (code "78") (name "unconnected-(U4-SDO{slash}SA0-PadP$7)") (class "Default")
      (node (ref "U4") (pin "P$7") (pinfunction "SDO/SA0_P$7") (pintype "bidirectional"))
    )
    (net (code "79") (name "unconnected-(U5-#SUSPEND-Pad15)") (class "Default")
      (node (ref "U5") (pin "15") (pinfunction "#SUSPEND_15") (pintype "bidirectional"))
    )
    (net (code "80") (name "unconnected-(U5-CTS-Pad18)") (class "Default")
      (node (ref "U5") (pin "18") (pinfunction "CTS_18") (pintype "bidirectional"))
    )
    (net (code "81") (name "unconnected-(U5-DCD-Pad24)") (class "Default")
      (node (ref "U5") (pin "24") (pinfunction "DCD_24") (pintype "bidirectional"))
    )
    (net (code "82") (name "unconnected-(U5-DSR-Pad22)") (class "Default")
      (node (ref "U5") (pin "22") (pinfunction "DSR_22") (pintype "bidirectional"))
    )
    (net (code "83") (name "unconnected-(U5-GPIO0{slash}TXLED-Pad14)") (class "Default")
      (node (ref "U5") (pin "14") (pinfunction "GPIO0/TXLED_14") (pintype "bidirectional"))
    )
    (net (code "84") (name "unconnected-(U5-GPIO1{slash}RXLED-Pad13)") (class "Default")
      (node (ref "U5") (pin "13") (pinfunction "GPIO1/RXLED_13") (pintype "bidirectional"))
    )
    (net (code "85") (name "unconnected-(U5-GPIO2-Pad12)") (class "Default")
      (node (ref "U5") (pin "12") (pinfunction "GPIO2_12") (pintype "bidirectional"))
    )
    (net (code "86") (name "unconnected-(U5-GPIO3-Pad11)") (class "Default")
      (node (ref "U5") (pin "11") (pinfunction "GPIO3_11") (pintype "bidirectional"))
    )
    (net (code "87") (name "unconnected-(U5-NC-Pad10)") (class "Default")
      (node (ref "U5") (pin "10") (pinfunction "NC_10") (pintype "bidirectional"))
    )
    (net (code "88") (name "unconnected-(U5-RI-Pad1)") (class "Default")
      (node (ref "U5") (pin "1") (pinfunction "RI_1") (pintype "bidirectional"))
    )
    (net (code "89") (name "unconnected-(U5-SUSPEND-Pad17)") (class "Default")
      (node (ref "U5") (pin "17") (pinfunction "SUSPEND_17") (pintype "bidirectional"))
    )
    (net (code "90") (name "unconnected-(U5-VPP-Pad16)") (class "Default")
      (node (ref "U5") (pin "16") (pinfunction "VPP_16") (pintype "bidirectional"))
    )
  )
)
